# BV100011_ControlQSPI.net
KiCad netlist of a schematic drawn in Altium Designer
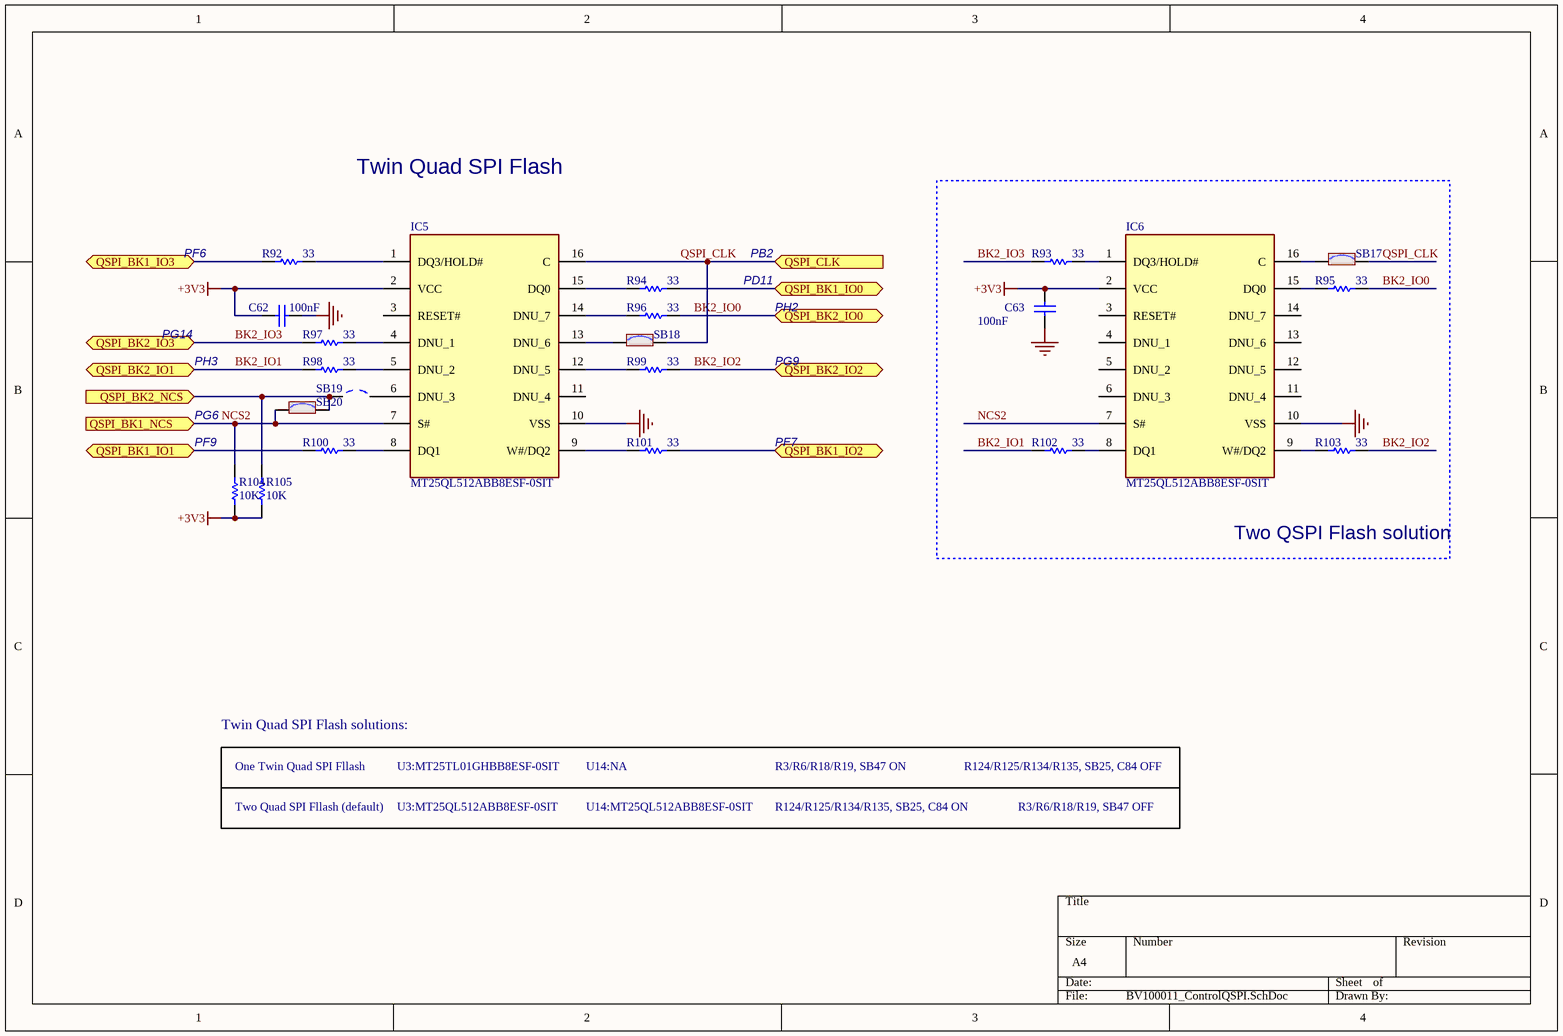
[diagram p0: BV100011_ControlQSPI.SchDoc]

(export (version "E")
  (design (tool "Eeschema 10.0.6"))
  (components
    (comp (ref "C62")
      (value "100nF")
      (footprint "C0402")
      (description "Capacitor")
      (fields (field (name "PUBLISHER") "Altium Limited"))
      (libsource (lib "Miscellaneous Devices") (part "Cap"))
    )
    (comp (ref "C63")
      (value "100nF")
      (footprint "C0402")
      (description "Capacitor")
      (fields (field (name "PUBLISHER") "Altium Limited"))
      (libsource (lib "Miscellaneous Devices") (part "Cap"))
    )
    (comp (ref "IC5")
      (value "MT25QL512ABB8ESF-0SIT")
      (footprint "SamacSys:SOIC127P1032X265-16N")
      (description "Integrated Circuit")
      (fields (field (name "MOUSER PART NUMBER") "340-278183-TRAY"))
      (libsource (lib "SamacSys") (part "MT25QL512ABB8ESF-0SIT"))
    )
    (comp (ref "IC6")
      (value "MT25QL512ABB8ESF-0SIT")
      (footprint "SamacSys:SOIC127P1032X265-16N")
      (description "Integrated Circuit")
      (fields (field (name "MOUSER PART NUMBER") "340-278183-TRAY"))
      (libsource (lib "SamacSys") (part "MT25QL512ABB8ESF-0SIT"))
    )
    (comp (ref "R92")
      (value "33")
      (footprint "R0402")
      (description "Resistor")
      (fields (field (name "PUBLISHER") "Altium Limited"))
      (libsource (lib "Miscellaneous Devices") (part "Res1"))
    )
    (comp (ref "R93")
      (value "33")
      (footprint "R0402")
      (description "Resistor")
      (fields (field (name "PUBLISHER") "Altium Limited"))
      (libsource (lib "Miscellaneous Devices") (part "Res1"))
    )
    (comp (ref "R94")
      (value "33")
      (footprint "R0402")
      (description "Resistor")
      (fields (field (name "PUBLISHER") "Altium Limited"))
      (libsource (lib "Miscellaneous Devices") (part "Res1"))
    )
    (comp (ref "R95")
      (value "33")
      (footprint "R0402")
      (description "Resistor")
      (fields (field (name "PUBLISHER") "Altium Limited"))
      (libsource (lib "Miscellaneous Devices") (part "Res1"))
    )
    (comp (ref "R96")
      (value "33")
      (footprint "R0402")
      (description "Resistor")
      (fields (field (name "PUBLISHER") "Altium Limited"))
      (libsource (lib "Miscellaneous Devices") (part "Res1"))
    )
    (comp (ref "R97")
      (value "33")
      (footprint "R0402")
      (description "Resistor")
      (fields (field (name "PUBLISHER") "Altium Limited"))
      (libsource (lib "Miscellaneous Devices") (part "Res1"))
    )
    (comp (ref "R98")
      (value "33")
      (footprint "R0402")
      (description "Resistor")
      (fields (field (name "PUBLISHER") "Altium Limited"))
      (libsource (lib "Miscellaneous Devices") (part "Res1"))
    )
    (comp (ref "R99")
      (value "33")
      (footprint "R0402")
      (description "Resistor")
      (fields (field (name "PUBLISHER") "Altium Limited"))
      (libsource (lib "Miscellaneous Devices") (part "Res1"))
    )
    (comp (ref "R100")
      (value "33")
      (footprint "R0402")
      (description "Resistor")
      (fields (field (name "PUBLISHER") "Altium Limited"))
      (libsource (lib "Miscellaneous Devices") (part "Res1"))
    )
    (comp (ref "R101")
      (value "33")
      (footprint "R0402")
      (description "Resistor")
      (fields (field (name "PUBLISHER") "Altium Limited"))
      (libsource (lib "Miscellaneous Devices") (part "Res1"))
    )
    (comp (ref "R102")
      (value "33")
      (footprint "R0402")
      (description "Resistor")
      (fields (field (name "PUBLISHER") "Altium Limited"))
      (libsource (lib "Miscellaneous Devices") (part "Res1"))
    )
    (comp (ref "R103")
      (value "33")
      (footprint "R0402")
      (description "Resistor")
      (fields (field (name "PUBLISHER") "Altium Limited"))
      (libsource (lib "Miscellaneous Devices") (part "Res1"))
    )
    (comp (ref "R104")
      (value "10K")
      (footprint "R0402")
      (description "Resistor,10K,0402,1%,1/16W")
      (fields
        (field (name "INTERNAL_PART_NUMBER") "MCD-00053")
        (field (name "MANUFACTURER_PART_NUMBER") "RC0402FR-0710KL")
        (field (name "PROVIDED_BY") "subcon")
      )
      (libsource (lib "MCD_PARTS_database") (part "Resistor"))
    )
    (comp (ref "R105")
      (value "10K")
      (footprint "R0402")
      (description "Resistor,10K,0402,1%,1/16W")
      (fields
        (field (name "INTERNAL_PART_NUMBER") "MCD-00053")
        (field (name "MANUFACTURER_PART_NUMBER") "RC0402FR-0710KL")
        (field (name "PROVIDED_BY") "subcon")
      )
      (libsource (lib "MCD_PARTS_database") (part "Resistor"))
    )
    (comp (ref "SB17")
      (value "Solder Bridge ON")
      (footprint "SB_0603")
      (libsource (lib "MCD_TOOLS") (part "SB_ON"))
    )
    (comp (ref "SB18")
      (value "Solder Bridge ON")
      (footprint "SB_0603")
      (libsource (lib "MCD_TOOLS") (part "SB_ON"))
    )
    (comp (ref "SB19")
      (value "Solder Bridge OFF")
      (footprint "SB_0603")
      (libsource (lib "MCD_TOOLS") (part "SB_OFF"))
    )
    (comp (ref "SB20")
      (value "Solder Bridge ON")
      (footprint "SB_0603")
      (libsource (lib "MCD_TOOLS") (part "SB_ON"))
    )
  )
  (nets
    (net (code "1") (name "+3V3") (class "Default")
      (node (ref "C62") (pin "1") (pinfunction "1_1") (pintype "passive"))
      (node (ref "C63") (pin "1") (pinfunction "1_1") (pintype "passive"))
      (node (ref "IC5") (pin "2") (pinfunction "VCC_2") (pintype "passive"))
      (node (ref "IC6") (pin "2") (pinfunction "VCC_2") (pintype "passive"))
      (node (ref "R104") (pin "1") (pinfunction "1_1") (pintype "passive"))
      (node (ref "R105") (pin "1") (pinfunction "1_1") (pintype "passive"))
    )
    (net (code "2") (name "/BK2_IO0") (class "Default")
      (node (ref "R95") (pin "1") (pinfunction "1_1") (pintype "passive"))
      (node (ref "R96") (pin "1") (pinfunction "1_1") (pintype "passive"))
    )
    (net (code "3") (name "/BK2_IO1") (class "Default")
      (node (ref "R102") (pin "2") (pinfunction "2_2") (pintype "passive"))
      (node (ref "R98") (pin "2") (pinfunction "2_2") (pintype "passive"))
    )
    (net (code "4") (name "/BK2_IO2") (class "Default")
      (node (ref "R103") (pin "1") (pinfunction "1_1") (pintype "passive"))
      (node (ref "R99") (pin "1") (pinfunction "1_1") (pintype "passive"))
    )
    (net (code "5") (name "/BK2_IO3") (class "Default")
      (node (ref "R93") (pin "2") (pinfunction "2_2") (pintype "passive"))
      (node (ref "R97") (pin "2") (pinfunction "2_2") (pintype "passive"))
    )
    (net (code "6") (name "/NCS2") (class "Default")
      (node (ref "IC5") (pin "7") (pinfunction "S#_7") (pintype "passive"))
      (node (ref "IC6") (pin "7") (pinfunction "S#_7") (pintype "passive"))
      (node (ref "R104") (pin "2") (pinfunction "2_2") (pintype "passive"))
      (node (ref "SB20") (pin "1") (pinfunction "1_1") (pintype "passive"))
    )
    (net (code "7") (name "/QSPI_BK1_IO0") (class "Default")
      (node (ref "R94") (pin "1") (pinfunction "1_1") (pintype "passive"))
    )
    (net (code "8") (name "/QSPI_BK1_IO1") (class "Default")
      (node (ref "R100") (pin "2") (pinfunction "2_2") (pintype "passive"))
    )
    (net (code "9") (name "/QSPI_BK1_IO2") (class "Default")
      (node (ref "R101") (pin "1") (pinfunction "1_1") (pintype "passive"))
    )
    (net (code "10") (name "/QSPI_BK1_IO3") (class "Default")
      (node (ref "R92") (pin "2") (pinfunction "2_2") (pintype "passive"))
    )
    (net (code "11") (name "/QSPI_BK2_NCS") (class "Default")
      (node (ref "R105") (pin "2") (pinfunction "2_2") (pintype "passive"))
      (node (ref "SB19") (pin "1") (pinfunction "1_1") (pintype "passive"))
      (node (ref "SB20") (pin "2") (pinfunction "2_2") (pintype "passive"))
    )
    (net (code "12") (name "/QSPI_CLK") (class "Default")
      (node (ref "IC5") (pin "16") (pinfunction "C_16") (pintype "passive"))
      (node (ref "SB17") (pin "2") (pinfunction "2_2") (pintype "passive"))
      (node (ref "SB18") (pin "2") (pinfunction "2_2") (pintype "passive"))
    )
    (net (code "13") (name "GND") (class "Default")
      (node (ref "C62") (pin "2") (pinfunction "2_2") (pintype "passive"))
      (node (ref "C63") (pin "2") (pinfunction "2_2") (pintype "passive"))
      (node (ref "IC5") (pin "10") (pinfunction "VSS_10") (pintype "passive"))
      (node (ref "IC6") (pin "10") (pinfunction "VSS_10") (pintype "passive"))
    )
    (net (code "14") (name "Net-(IC5-DNU_1)") (class "Default")
      (node (ref "IC5") (pin "4") (pinfunction "DNU_1_4") (pintype "passive"))
      (node (ref "R97") (pin "1") (pinfunction "1_1") (pintype "passive"))
    )
    (net (code "15") (name "Net-(IC5-DNU_2)") (class "Default")
      (node (ref "IC5") (pin "5") (pinfunction "DNU_2_5") (pintype "passive"))
      (node (ref "R98") (pin "1") (pinfunction "1_1") (pintype "passive"))
    )
    (net (code "16") (name "Net-(IC5-DNU_3)") (class "Default")
      (node (ref "IC5") (pin "6") (pinfunction "DNU_3_6") (pintype "passive"))
      (node (ref "SB19") (pin "2") (pinfunction "2_2") (pintype "passive"))
    )
    (net (code "17") (name "Net-(IC5-DNU_5)") (class "Default")
      (node (ref "IC5") (pin "12") (pinfunction "DNU_5_12") (pintype "passive"))
      (node (ref "R99") (pin "2") (pinfunction "2_2") (pintype "passive"))
    )
    (net (code "18") (name "Net-(IC5-DNU_6)") (class "Default")
      (node (ref "IC5") (pin "13") (pinfunction "DNU_6_13") (pintype "passive"))
      (node (ref "SB18") (pin "1") (pinfunction "1_1") (pintype "passive"))
    )
    (net (code "19") (name "Net-(IC5-DNU_7)") (class "Default")
      (node (ref "IC5") (pin "14") (pinfunction "DNU_7_14") (pintype "passive"))
      (node (ref "R96") (pin "2") (pinfunction "2_2") (pintype "passive"))
    )
    (net (code "20") (name "Net-(IC5-DQ0)") (class "Default")
      (node (ref "IC5") (pin "15") (pinfunction "DQ0_15") (pintype "passive"))
      (node (ref "R94") (pin "2") (pinfunction "2_2") (pintype "passive"))
    )
    (net (code "21") (name "Net-(IC5-DQ1)") (class "Default")
      (node (ref "IC5") (pin "8") (pinfunction "DQ1_8") (pintype "passive"))
      (node (ref "R100") (pin "1") (pinfunction "1_1") (pintype "passive"))
    )
    (net (code "22") (name "Net-(IC5-DQ3{slash}HOLD#)") (class "Default")
      (node (ref "IC5") (pin "1") (pinfunction "DQ3/HOLD#_1") (pintype "passive"))
      (node (ref "R92") (pin "1") (pinfunction "1_1") (pintype "passive"))
    )
    (net (code "23") (name "Net-(IC5-W#{slash}DQ2)") (class "Default")
      (node (ref "IC5") (pin "9") (pinfunction "W#/DQ2_9") (pintype "passive"))
      (node (ref "R101") (pin "2") (pinfunction "2_2") (pintype "passive"))
    )
    (net (code "24") (name "Net-(IC6-C)") (class "Default")
      (node (ref "IC6") (pin "16") (pinfunction "C_16") (pintype "passive"))
      (node (ref "SB17") (pin "1") (pinfunction "1_1") (pintype "passive"))
    )
    (net (code "25") (name "Net-(IC6-DQ0)") (class "Default")
      (node (ref "IC6") (pin "15") (pinfunction "DQ0_15") (pintype "passive"))
      (node (ref "R95") (pin "2") (pinfunction "2_2") (pintype "passive"))
    )
    (net (code "26") (name "Net-(IC6-DQ1)") (class "Default")
      (node (ref "IC6") (pin "8") (pinfunction "DQ1_8") (pintype "passive"))
      (node (ref "R102") (pin "1") (pinfunction "1_1") (pintype "passive"))
    )
    (net (code "27") (name "Net-(IC6-DQ3{slash}HOLD#)") (class "Default")
      (node (ref "IC6") (pin "1") (pinfunction "DQ3/HOLD#_1") (pintype "passive"))
      (node (ref "R93") (pin "1") (pinfunction "1_1") (pintype "passive"))
    )
    (net (code "28") (name "Net-(IC6-W#{slash}DQ2)") (class "Default")
      (node (ref "IC6") (pin "9") (pinfunction "W#/DQ2_9") (pintype "passive"))
      (node (ref "R103") (pin "2") (pinfunction "2_2") (pintype "passive"))
    )
    (net (code "29") (name "unconnected-(IC5-DNU_4-Pad11)") (class "Default")
      (node (ref "IC5") (pin "11") (pinfunction "DNU_4_11") (pintype "passive"))
    )
    (net (code "30") (name "unconnected-(IC5-RESET#-Pad3)") (class "Default")
      (node (ref "IC5") (pin "3") (pinfunction "RESET#_3") (pintype "passive"))
    )
    (net (code "31") (name "unconnected-(IC6-DNU_1-Pad4)") (class "Default")
      (node (ref "IC6") (pin "4") (pinfunction "DNU_1_4") (pintype "passive"))
    )
    (net (code "32") (name "unconnected-(IC6-DNU_2-Pad5)") (class "Default")
      (node (ref "IC6") (pin "5") (pinfunction "DNU_2_5") (pintype "passive"))
    )
    (net (code "33") (name "unconnected-(IC6-DNU_3-Pad6)") (class "Default")
      (node (ref "IC6") (pin "6") (pinfunction "DNU_3_6") (pintype "passive"))
    )
    (net (code "34") (name "unconnected-(IC6-DNU_4-Pad11)") (class "Default")
      (node (ref "IC6") (pin "11") (pinfunction "DNU_4_11") (pintype "passive"))
    )
    (net (code "35") (name "unconnected-(IC6-DNU_5-Pad12)") (class "Default")
      (node (ref "IC6") (pin "12") (pinfunction "DNU_5_12") (pintype "passive"))
    )
    (net (code "36") (name "unconnected-(IC6-DNU_6-Pad13)") (class "Default")
      (node (ref "IC6") (pin "13") (pinfunction "DNU_6_13") (pintype "passive"))
    )
    (net (code "37") (name "unconnected-(IC6-DNU_7-Pad14)") (class "Default")
      (node (ref "IC6") (pin "14") (pinfunction "DNU_7_14") (pintype "passive"))
    )
    (net (code "38") (name "unconnected-(IC6-RESET#-Pad3)") (class "Default")
      (node (ref "IC6") (pin "3") (pinfunction "RESET#_3") (pintype "passive"))
    )
  )
)
